# KX1_DualDeployAltimeter_v100.net
KiCad netlist of a schematic drawn in EAGLE
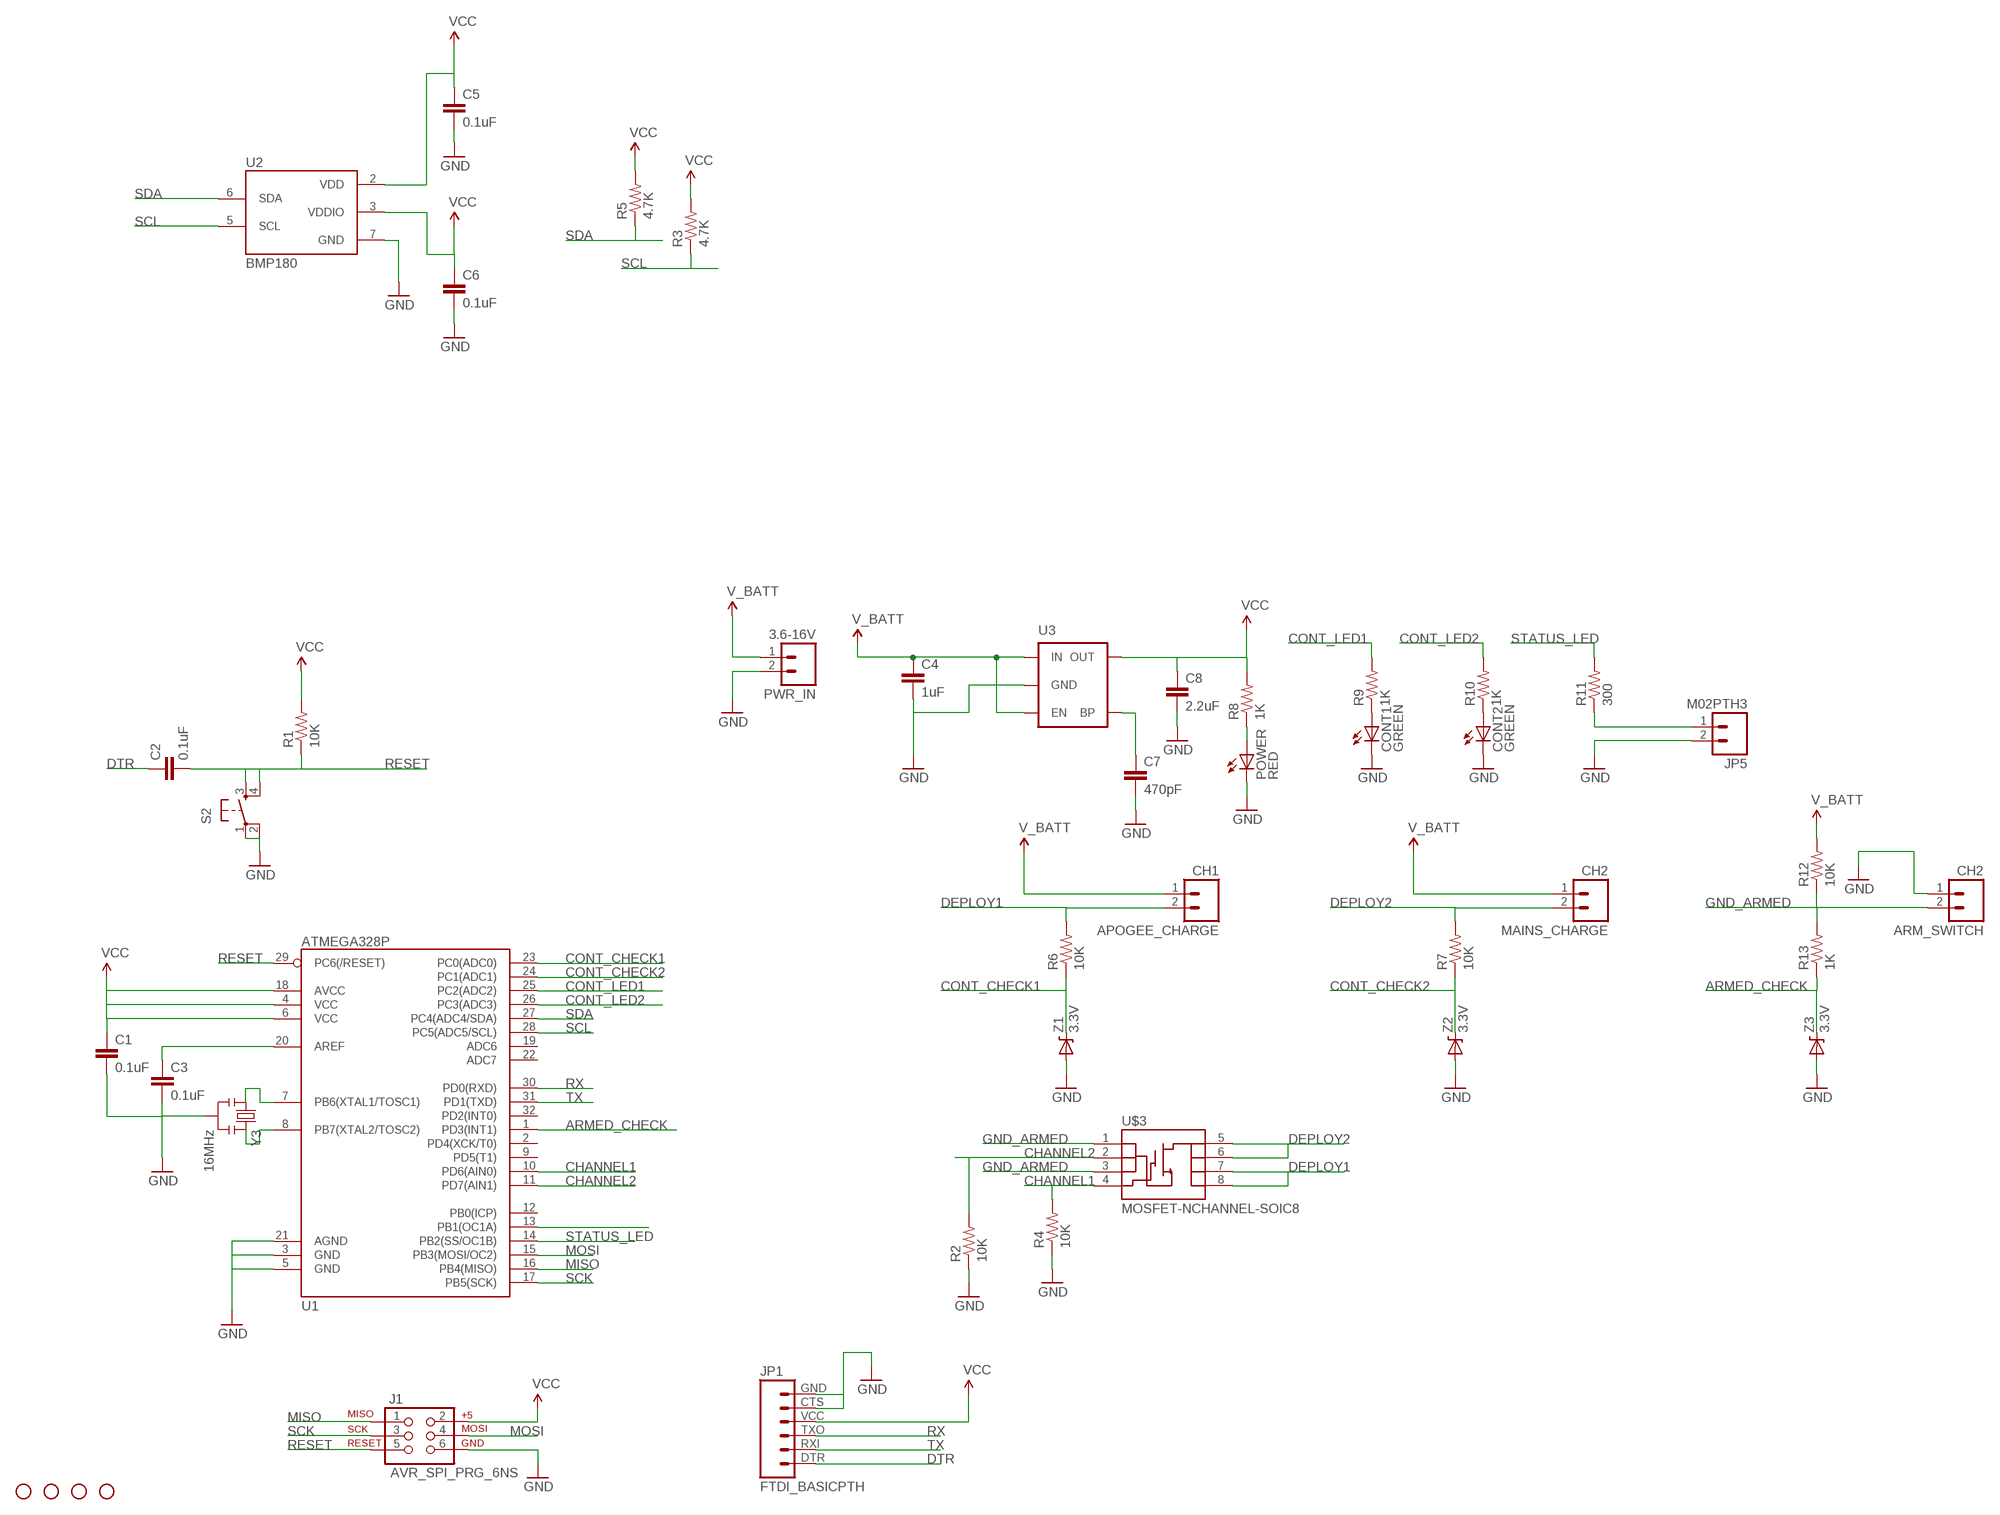
[diagram p0: schematic, sheet 1]

(export (version "E")
  (design (tool "Eeschema 10.0.6"))
  (components
    (comp (ref "APOGEE_CHARGE")
      (value "CH1")
      (footprint "eagle-import:1X02_LONGPADS")
      (libsource (lib "eagle-import") (part "M02PTH3"))
    )
    (comp (ref "ARM_SWITCH")
      (value "CH2")
      (footprint "eagle-import:1X02_LONGPADS")
      (libsource (lib "eagle-import") (part "M02PTH3"))
    )
    (comp (ref "C1")
      (value "0.1uF")
      (footprint "eagle-import:0603-CAP")
      (libsource (lib "eagle-import") (part "CAP0603-CAP"))
    )
    (comp (ref "C2")
      (value "0.1uF")
      (footprint "eagle-import:0603-CAP")
      (libsource (lib "eagle-import") (part "CAP0603-CAP"))
    )
    (comp (ref "C3")
      (value "0.1uF")
      (footprint "eagle-import:0603-CAP")
      (libsource (lib "eagle-import") (part "0.1UF-25V(+80/-20%)(0603)"))
    )
    (comp (ref "C4")
      (value "1uF")
      (footprint "eagle-import:0603-CAP")
      (libsource (lib "eagle-import") (part "CAP0603-CAP"))
    )
    (comp (ref "C5")
      (value "0.1uF")
      (footprint "eagle-import:0603-CAP")
      (libsource (lib "eagle-import") (part "CAP0603-CAP"))
    )
    (comp (ref "C6")
      (value "0.1uF")
      (footprint "eagle-import:0603-CAP")
      (libsource (lib "eagle-import") (part "CAP0603-CAP"))
    )
    (comp (ref "C7")
      (value "470pF")
      (footprint "eagle-import:0603-CAP")
      (libsource (lib "eagle-import") (part "CAP0603-CAP"))
    )
    (comp (ref "C8")
      (value "2.2uF")
      (footprint "eagle-import:0603-CAP")
      (libsource (lib "eagle-import") (part "CAP0603-CAP"))
    )
    (comp (ref "CONT1")
      (value "GREEN")
      (footprint "eagle-import:LED-0603")
      (libsource (lib "eagle-import") (part "LED0603"))
    )
    (comp (ref "CONT2")
      (value "GREEN")
      (footprint "eagle-import:LED-0603")
      (libsource (lib "eagle-import") (part "LED0603"))
    )
    (comp (ref "J1")
      (value "AVR_SPI_PRG_6NS")
      (footprint "eagle-import:2X3-NS")
      (libsource (lib "eagle-import") (part "AVR_SPI_PRG_6NS"))
    )
    (comp (ref "JP1")
      (value "FTDI_BASICPTH")
      (footprint "eagle-import:FTDI_BASIC")
      (libsource (lib "eagle-import") (part "FTDI_BASICPTH"))
    )
    (comp (ref "JP5")
      (value "M02PTH3")
      (footprint "eagle-import:1X02_LONGPADS")
      (libsource (lib "eagle-import") (part "M02PTH3"))
    )
    (comp (ref "MAINS_CHARGE")
      (value "CH2")
      (footprint "eagle-import:1X02_LONGPADS")
      (libsource (lib "eagle-import") (part "M02PTH3"))
    )
    (comp (ref "POWER")
      (value "RED")
      (footprint "eagle-import:LED-0603")
      (libsource (lib "eagle-import") (part "LED0603"))
    )
    (comp (ref "PWR_IN")
      (value "3.6-16V")
      (footprint "eagle-import:1X02_LONGPADS")
      (libsource (lib "eagle-import") (part "M02PTH3"))
    )
    (comp (ref "R1")
      (value "10K")
      (footprint "eagle-import:0603-RES")
      (libsource (lib "eagle-import") (part "RESISTOR0603"))
    )
    (comp (ref "R2")
      (value "10K")
      (footprint "eagle-import:0603-RES")
      (libsource (lib "eagle-import") (part "RESISTOR0603"))
    )
    (comp (ref "R3")
      (value "4.7K")
      (footprint "eagle-import:0603-RES")
      (libsource (lib "eagle-import") (part "RESISTOR0603"))
    )
    (comp (ref "R4")
      (value "10K")
      (footprint "eagle-import:0603-RES")
      (libsource (lib "eagle-import") (part "RESISTOR0603"))
    )
    (comp (ref "R5")
      (value "4.7K")
      (footprint "eagle-import:0603-RES")
      (libsource (lib "eagle-import") (part "RESISTOR0603"))
    )
    (comp (ref "R6")
      (value "10K")
      (footprint "eagle-import:0603-RES")
      (libsource (lib "eagle-import") (part "RESISTOR0603-RES"))
    )
    (comp (ref "R7")
      (value "10K")
      (footprint "eagle-import:0603-RES")
      (libsource (lib "eagle-import") (part "RESISTOR0603-RES"))
    )
    (comp (ref "R8")
      (value "1K")
      (footprint "eagle-import:0603-RES")
      (libsource (lib "eagle-import") (part "RESISTOR0603-RES"))
    )
    (comp (ref "R9")
      (value "1K")
      (footprint "eagle-import:0603-RES")
      (libsource (lib "eagle-import") (part "RESISTOR0603-RES"))
    )
    (comp (ref "R10")
      (value "1K")
      (footprint "eagle-import:0603-RES")
      (libsource (lib "eagle-import") (part "RESISTOR0603-RES"))
    )
    (comp (ref "R11")
      (value "300")
      (footprint "eagle-import:0603-RES")
      (libsource (lib "eagle-import") (part "RESISTOR0603-RES"))
    )
    (comp (ref "R12")
      (value "10K")
      (footprint "eagle-import:0603-RES")
      (libsource (lib "eagle-import") (part "RESISTOR0603"))
    )
    (comp (ref "R13")
      (value "1K")
      (footprint "eagle-import:0603-RES")
      (libsource (lib "eagle-import") (part "RESISTOR0603-RES"))
    )
    (comp (ref "S2")
      (value "TAC_SWITCHPTH")
      (footprint "eagle-import:TACTILE-PTH")
      (libsource (lib "eagle-import") (part "TAC_SWITCHPTH"))
    )
    (comp (ref "STANDOFF1")
      (value "STAND-OFF")
      (footprint "eagle-import:STAND-OFF")
      (libsource (lib "eagle-import") (part "STAND-OFF"))
    )
    (comp (ref "STANDOFF2")
      (value "STAND-OFF")
      (footprint "eagle-import:STAND-OFF")
      (libsource (lib "eagle-import") (part "STAND-OFF"))
    )
    (comp (ref "STANDOFF3")
      (value "STAND-OFF")
      (footprint "eagle-import:STAND-OFF")
      (libsource (lib "eagle-import") (part "STAND-OFF"))
    )
    (comp (ref "STANDOFF4")
      (value "STAND-OFF")
      (footprint "eagle-import:STAND-OFF")
      (libsource (lib "eagle-import") (part "STAND-OFF"))
    )
    (comp (ref "U$3")
      (value "MOSFET-NCHANNEL-SOIC8")
      (footprint "eagle-import:SO08")
      (libsource (lib "eagle-import") (part "MOSFET-NCHANNEL-SOIC8"))
    )
    (comp (ref "U1")
      (value "ATMEGA328P")
      (footprint "eagle-import:TQFP32-08")
      (libsource (lib "eagle-import") (part "ATMEGA328_SMT"))
    )
    (comp (ref "U2")
      (value "BMP180")
      (footprint "eagle-import:BMP180")
      (libsource (lib "eagle-import") (part "BMP180"))
    )
    (comp (ref "U3")
      (value "MIC52053.3V")
      (footprint "eagle-import:SOT23-5")
      (libsource (lib "eagle-import") (part "MIC52053.3V"))
    )
    (comp (ref "Y3")
      (value "16MHz")
      (footprint "eagle-import:RESONATOR-SMD")
      (libsource (lib "eagle-import") (part "RESONATOR16MHZ"))
    )
    (comp (ref "Z1")
      (value "3.3V")
      (footprint "eagle-import:SOD-323")
      (libsource (lib "eagle-import") (part "DIODE-ZENER-BZT52"))
    )
    (comp (ref "Z2")
      (value "3.3V")
      (footprint "eagle-import:SOD-323")
      (libsource (lib "eagle-import") (part "DIODE-ZENER-BZT52"))
    )
    (comp (ref "Z3")
      (value "3.3V")
      (footprint "eagle-import:SOD-323")
      (libsource (lib "eagle-import") (part "DIODE-ZENER-BZT52"))
    )
  )
  (nets
    (net (code "1") (name "/ARMED_CHECK") (class "Default")
      (node (ref "R13") (pin "1") (pinfunction "1_1") (pintype "passive"))
      (node (ref "U1") (pin "1") (pinfunction "PD3(INT1)_1") (pintype "bidirectional"))
      (node (ref "Z3") (pin "1") (pinfunction "C_1") (pintype "passive"))
    )
    (net (code "2") (name "/CHANNEL1") (class "Default")
      (node (ref "R4") (pin "2") (pinfunction "2_2") (pintype "passive"))
      (node (ref "U$3") (pin "4") (pinfunction "G_4") (pintype "bidirectional"))
      (node (ref "U1") (pin "10") (pinfunction "PD6(AIN0)_10") (pintype "bidirectional"))
    )
    (net (code "3") (name "/CHANNEL2") (class "Default")
      (node (ref "R2") (pin "2") (pinfunction "2_2") (pintype "passive"))
      (node (ref "U$3") (pin "2") (pinfunction "S_2") (pintype "bidirectional"))
      (node (ref "U1") (pin "11") (pinfunction "PD7(AIN1)_11") (pintype "bidirectional"))
    )
    (net (code "4") (name "/CONT_CHECK1") (class "Default")
      (node (ref "R6") (pin "1") (pinfunction "1_1") (pintype "passive"))
      (node (ref "U1") (pin "23") (pinfunction "PC0(ADC0)_23") (pintype "bidirectional"))
      (node (ref "Z1") (pin "1") (pinfunction "C_1") (pintype "passive"))
    )
    (net (code "5") (name "/CONT_CHECK2") (class "Default")
      (node (ref "R7") (pin "1") (pinfunction "1_1") (pintype "passive"))
      (node (ref "U1") (pin "24") (pinfunction "PC1(ADC1)_24") (pintype "bidirectional"))
      (node (ref "Z2") (pin "1") (pinfunction "C_1") (pintype "passive"))
    )
    (net (code "6") (name "/CONT_LED1") (class "Default")
      (node (ref "R9") (pin "2") (pinfunction "2_2") (pintype "passive"))
      (node (ref "U1") (pin "25") (pinfunction "PC2(ADC2)_25") (pintype "bidirectional"))
    )
    (net (code "7") (name "/CONT_LED2") (class "Default")
      (node (ref "R10") (pin "2") (pinfunction "2_2") (pintype "passive"))
      (node (ref "U1") (pin "26") (pinfunction "PC3(ADC3)_26") (pintype "bidirectional"))
    )
    (net (code "8") (name "/DEPLOY1") (class "Default")
      (node (ref "APOGEE_CHARGE") (pin "2") (pinfunction "2_2") (pintype "passive"))
      (node (ref "R6") (pin "2") (pinfunction "2_2") (pintype "passive"))
      (node (ref "U$3") (pin "7") (pinfunction "D_7") (pintype "bidirectional"))
      (node (ref "U$3") (pin "8") (pinfunction "D_8") (pintype "bidirectional"))
    )
    (net (code "9") (name "/DEPLOY2") (class "Default")
      (node (ref "MAINS_CHARGE") (pin "2") (pinfunction "2_2") (pintype "passive"))
      (node (ref "R7") (pin "2") (pinfunction "2_2") (pintype "passive"))
      (node (ref "U$3") (pin "5") (pinfunction "D_5") (pintype "bidirectional"))
      (node (ref "U$3") (pin "6") (pinfunction "D_6") (pintype "bidirectional"))
    )
    (net (code "10") (name "/DTR") (class "Default")
      (node (ref "C2") (pin "1") (pinfunction "1_1") (pintype "passive"))
      (node (ref "JP1") (pin "DTR") (pinfunction "1_DTR") (pintype "passive"))
    )
    (net (code "11") (name "/GND_ARMED") (class "Default")
      (node (ref "ARM_SWITCH") (pin "2") (pinfunction "2_2") (pintype "passive"))
      (node (ref "R12") (pin "1") (pinfunction "1_1") (pintype "passive"))
      (node (ref "R13") (pin "2") (pinfunction "2_2") (pintype "passive"))
      (node (ref "U$3") (pin "1") (pinfunction "S_1") (pintype "bidirectional"))
      (node (ref "U$3") (pin "3") (pinfunction "S_3") (pintype "bidirectional"))
    )
    (net (code "12") (name "/MISO") (class "Default")
      (node (ref "J1") (pin "1") (pinfunction "1_1") (pintype "passive"))
      (node (ref "U1") (pin "16") (pinfunction "PB4(MISO)_16") (pintype "bidirectional"))
    )
    (net (code "13") (name "/MOSI") (class "Default")
      (node (ref "J1") (pin "4") (pinfunction "4_4") (pintype "passive"))
      (node (ref "U1") (pin "15") (pinfunction "PB3(MOSI/OC2)_15") (pintype "bidirectional"))
    )
    (net (code "14") (name "/RESET") (class "Default")
      (node (ref "C2") (pin "2") (pinfunction "2_2") (pintype "passive"))
      (node (ref "J1") (pin "5") (pinfunction "5_5") (pintype "passive"))
      (node (ref "R1") (pin "1") (pinfunction "1_1") (pintype "passive"))
      (node (ref "S2") (pin "3") (pinfunction "3_3") (pintype "passive"))
      (node (ref "S2") (pin "4") (pinfunction "4_4") (pintype "passive"))
      (node (ref "U1") (pin "29") (pinfunction "PC6(/RESET)_29") (pintype "bidirectional"))
    )
    (net (code "15") (name "/RX") (class "Default")
      (node (ref "JP1") (pin "TXO") (pinfunction "3_TXO") (pintype "passive"))
      (node (ref "U1") (pin "30") (pinfunction "PD0(RXD)_30") (pintype "bidirectional"))
    )
    (net (code "16") (name "/SCK") (class "Default")
      (node (ref "J1") (pin "3") (pinfunction "3_3") (pintype "passive"))
      (node (ref "U1") (pin "17") (pinfunction "PB5(SCK)_17") (pintype "bidirectional"))
    )
    (net (code "17") (name "/SCL") (class "Default")
      (node (ref "R3") (pin "1") (pinfunction "1_1") (pintype "passive"))
      (node (ref "U1") (pin "28") (pinfunction "PC5(ADC5/SCL)_28") (pintype "bidirectional"))
      (node (ref "U2") (pin "5") (pinfunction "SCL_5") (pintype "input"))
    )
    (net (code "18") (name "/SDA") (class "Default")
      (node (ref "R5") (pin "1") (pinfunction "1_1") (pintype "passive"))
      (node (ref "U1") (pin "27") (pinfunction "PC4(ADC4/SDA)_27") (pintype "bidirectional"))
      (node (ref "U2") (pin "6") (pinfunction "SDA_6") (pintype "bidirectional"))
    )
    (net (code "19") (name "/STATUS_LED") (class "Default")
      (node (ref "R11") (pin "2") (pinfunction "2_2") (pintype "passive"))
      (node (ref "U1") (pin "14") (pinfunction "PB2(SS/OC1B)_14") (pintype "bidirectional"))
    )
    (net (code "20") (name "/TX") (class "Default")
      (node (ref "JP1") (pin "RXI") (pinfunction "2_RXI") (pintype "passive"))
      (node (ref "U1") (pin "31") (pinfunction "PD1(TXD)_31") (pintype "bidirectional"))
    )
    (net (code "21") (name "GND") (class "Default")
      (node (ref "ARM_SWITCH") (pin "1") (pinfunction "1_1") (pintype "passive"))
      (node (ref "C1") (pin "2") (pinfunction "2_2") (pintype "passive"))
      (node (ref "C3") (pin "2") (pinfunction "2_2") (pintype "passive"))
      (node (ref "C4") (pin "2") (pinfunction "2_2") (pintype "passive"))
      (node (ref "C5") (pin "2") (pinfunction "2_2") (pintype "passive"))
      (node (ref "C6") (pin "2") (pinfunction "2_2") (pintype "passive"))
      (node (ref "C7") (pin "2") (pinfunction "2_2") (pintype "passive"))
      (node (ref "C8") (pin "2") (pinfunction "2_2") (pintype "passive"))
      (node (ref "CONT1") (pin "C") (pinfunction "C_C") (pintype "passive"))
      (node (ref "CONT2") (pin "C") (pinfunction "C_C") (pintype "passive"))
      (node (ref "J1") (pin "6") (pinfunction "6_6") (pintype "passive"))
      (node (ref "JP1") (pin "CTS") (pinfunction "5_CTS") (pintype "passive"))
      (node (ref "JP1") (pin "GND") (pinfunction "6_GND") (pintype "passive"))
      (node (ref "JP5") (pin "2") (pinfunction "2_2") (pintype "passive"))
      (node (ref "POWER") (pin "C") (pinfunction "C_C") (pintype "passive"))
      (node (ref "PWR_IN") (pin "2") (pinfunction "2_2") (pintype "passive"))
      (node (ref "R2") (pin "1") (pinfunction "1_1") (pintype "passive"))
      (node (ref "R4") (pin "1") (pinfunction "1_1") (pintype "passive"))
      (node (ref "S2") (pin "1") (pinfunction "1_1") (pintype "passive"))
      (node (ref "S2") (pin "2") (pinfunction "2_2") (pintype "passive"))
      (node (ref "U1") (pin "21") (pinfunction "AGND_21") (pintype "bidirectional"))
      (node (ref "U1") (pin "3") (pinfunction "GND_3") (pintype "bidirectional"))
      (node (ref "U1") (pin "5") (pinfunction "GND_5") (pintype "bidirectional"))
      (node (ref "U2") (pin "7") (pinfunction "GND_7") (pintype "power_in"))
      (node (ref "U3") (pin "2") (pinfunction "GND_2") (pintype "input"))
      (node (ref "Y3") (pin "2") (pinfunction "2_2") (pintype "passive"))
      (node (ref "Z1") (pin "2") (pinfunction "A_2") (pintype "passive"))
      (node (ref "Z2") (pin "2") (pinfunction "A_2") (pintype "passive"))
      (node (ref "Z3") (pin "2") (pinfunction "A_2") (pintype "passive"))
    )
    (net (code "22") (name "Net-(CONT1-PadA)") (class "Default")
      (node (ref "CONT1") (pin "A") (pinfunction "A_A") (pintype "passive"))
      (node (ref "R9") (pin "1") (pinfunction "1_1") (pintype "passive"))
    )
    (net (code "23") (name "Net-(CONT2-PadA)") (class "Default")
      (node (ref "CONT2") (pin "A") (pinfunction "A_A") (pintype "passive"))
      (node (ref "R10") (pin "1") (pinfunction "1_1") (pintype "passive"))
    )
    (net (code "24") (name "Net-(JP5-Pad1)") (class "Default")
      (node (ref "JP5") (pin "1") (pinfunction "1_1") (pintype "passive"))
      (node (ref "R11") (pin "1") (pinfunction "1_1") (pintype "passive"))
    )
    (net (code "25") (name "Net-(POWER-PadA)") (class "Default")
      (node (ref "POWER") (pin "A") (pinfunction "A_A") (pintype "passive"))
      (node (ref "R8") (pin "1") (pinfunction "1_1") (pintype "passive"))
    )
    (net (code "26") (name "Net-(U1-AREF)") (class "Default")
      (node (ref "C3") (pin "1") (pinfunction "1_1") (pintype "passive"))
      (node (ref "U1") (pin "20") (pinfunction "AREF_20") (pintype "bidirectional"))
    )
    (net (code "27") (name "Net-(U1-PB6(XTAL1{slash}TOSC1))") (class "Default")
      (node (ref "U1") (pin "7") (pinfunction "PB6(XTAL1/TOSC1)_7") (pintype "bidirectional"))
      (node (ref "Y3") (pin "1") (pinfunction "1_1") (pintype "passive"))
    )
    (net (code "28") (name "Net-(U1-PB7(XTAL2{slash}TOSC2))") (class "Default")
      (node (ref "U1") (pin "8") (pinfunction "PB7(XTAL2/TOSC2)_8") (pintype "bidirectional"))
      (node (ref "Y3") (pin "3") (pinfunction "3_3") (pintype "passive"))
    )
    (net (code "29") (name "Net-(U3-BP)") (class "Default")
      (node (ref "C7") (pin "1") (pinfunction "1_1") (pintype "passive"))
      (node (ref "U3") (pin "4") (pinfunction "BP_4") (pintype "input"))
    )
    (net (code "30") (name "VCC") (class "Default")
      (node (ref "C1") (pin "1") (pinfunction "1_1") (pintype "passive"))
      (node (ref "C5") (pin "1") (pinfunction "1_1") (pintype "passive"))
      (node (ref "C6") (pin "1") (pinfunction "1_1") (pintype "passive"))
      (node (ref "C8") (pin "1") (pinfunction "1_1") (pintype "passive"))
      (node (ref "J1") (pin "2") (pinfunction "2_2") (pintype "passive"))
      (node (ref "JP1") (pin "VCC") (pinfunction "4_VCC") (pintype "passive"))
      (node (ref "R1") (pin "2") (pinfunction "2_2") (pintype "passive"))
      (node (ref "R3") (pin "2") (pinfunction "2_2") (pintype "passive"))
      (node (ref "R5") (pin "2") (pinfunction "2_2") (pintype "passive"))
      (node (ref "R8") (pin "2") (pinfunction "2_2") (pintype "passive"))
      (node (ref "U1") (pin "18") (pinfunction "AVCC_18") (pintype "bidirectional"))
      (node (ref "U1") (pin "4") (pinfunction "VCC_4") (pintype "bidirectional"))
      (node (ref "U1") (pin "6") (pinfunction "VCC_6") (pintype "bidirectional"))
      (node (ref "U2") (pin "2") (pinfunction "VDD_2") (pintype "power_in"))
      (node (ref "U2") (pin "3") (pinfunction "VDDIO_3") (pintype "power_in"))
      (node (ref "U3") (pin "5") (pinfunction "OUT_5") (pintype "passive"))
    )
    (net (code "31") (name "V_BATT") (class "Default")
      (node (ref "APOGEE_CHARGE") (pin "1") (pinfunction "1_1") (pintype "passive"))
      (node (ref "C4") (pin "1") (pinfunction "1_1") (pintype "passive"))
      (node (ref "MAINS_CHARGE") (pin "1") (pinfunction "1_1") (pintype "passive"))
      (node (ref "PWR_IN") (pin "1") (pinfunction "1_1") (pintype "passive"))
      (node (ref "R12") (pin "2") (pinfunction "2_2") (pintype "passive"))
      (node (ref "U3") (pin "1") (pinfunction "IN_1") (pintype "input"))
      (node (ref "U3") (pin "3") (pinfunction "EN_3") (pintype "input"))
    )
    (net (code "32") (name "unconnected-(U1-ADC6-Pad19)") (class "Default")
      (node (ref "U1") (pin "19") (pinfunction "ADC6_19") (pintype "bidirectional"))
    )
    (net (code "33") (name "unconnected-(U1-ADC7-Pad22)") (class "Default")
      (node (ref "U1") (pin "22") (pinfunction "ADC7_22") (pintype "bidirectional"))
    )
    (net (code "34") (name "unconnected-(U1-PB0(ICP)-Pad12)") (class "Default")
      (node (ref "U1") (pin "12") (pinfunction "PB0(ICP)_12") (pintype "bidirectional"))
    )
    (net (code "35") (name "unconnected-(U1-PB1(OC1A)-Pad13)") (class "Default")
      (node (ref "U1") (pin "13") (pinfunction "PB1(OC1A)_13") (pintype "bidirectional"))
    )
    (net (code "36") (name "unconnected-(U1-PD2(INT0)-Pad32)") (class "Default")
      (node (ref "U1") (pin "32") (pinfunction "PD2(INT0)_32") (pintype "bidirectional"))
    )
    (net (code "37") (name "unconnected-(U1-PD4(XCK{slash}T0)-Pad2)") (class "Default")
      (node (ref "U1") (pin "2") (pinfunction "PD4(XCK/T0)_2") (pintype "bidirectional"))
    )
    (net (code "38") (name "unconnected-(U1-PD5(T1)-Pad9)") (class "Default")
      (node (ref "U1") (pin "9") (pinfunction "PD5(T1)_9") (pintype "bidirectional"))
    )
  )
)
